# microBat.net
KiCad netlist of a schematic drawn in EAGLE
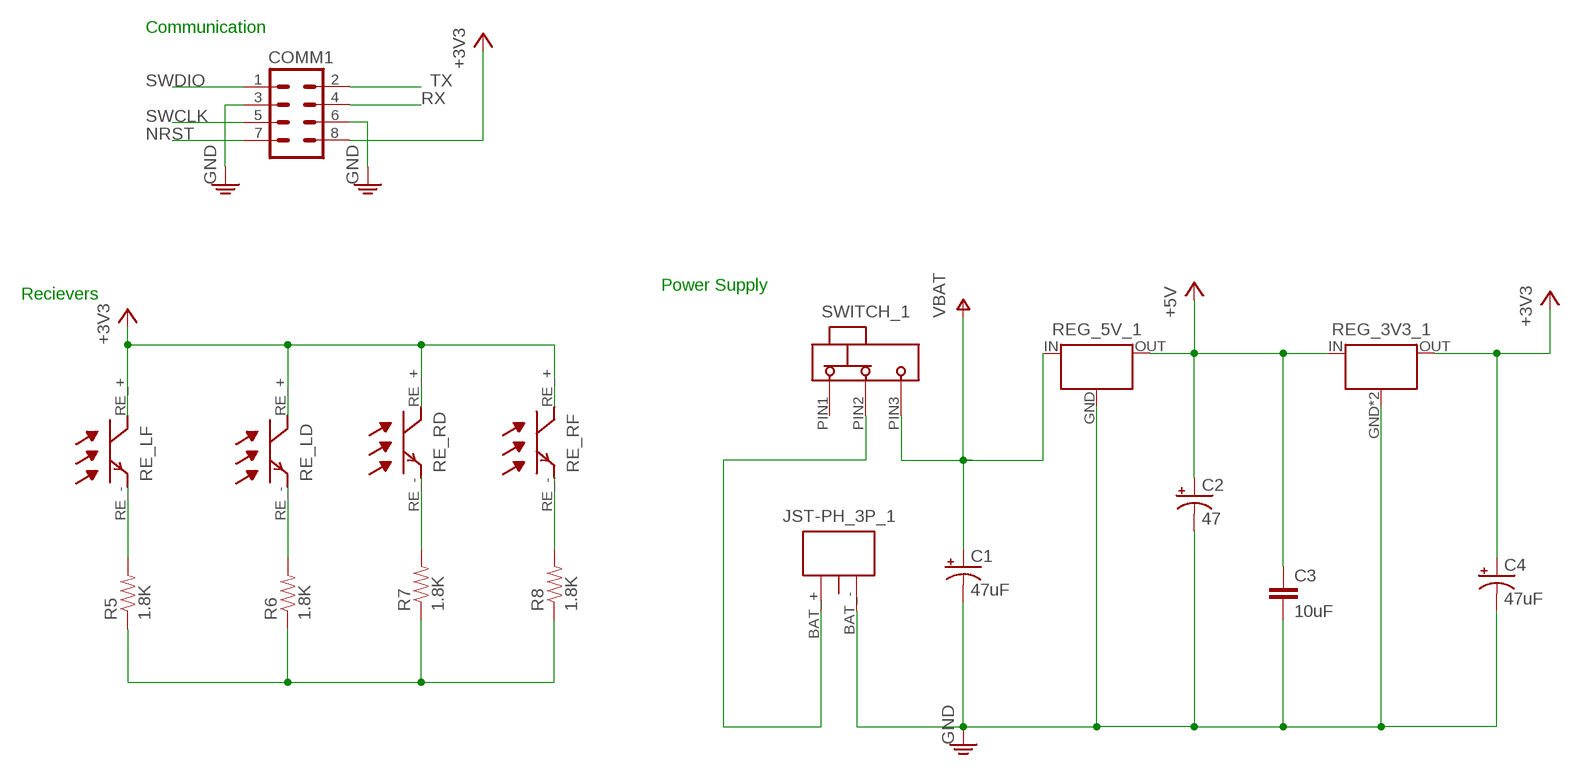
[diagram p0: schematic, sheet 1]

(export (version "E")
  (design (tool "Eeschema 10.0.6"))
  (components
    (comp (ref "C1")
      (value "47uF")
      (footprint "eagle-import:CAP_TANT_1210IN_3528MM")
      (libsource (lib "eagle-import") (part "CAP_TANT_1210IN_3528MM"))
    )
    (comp (ref "C2")
      (value "47")
      (footprint "eagle-import:CAP_TANT_1210IN_3528MM")
      (libsource (lib "eagle-import") (part "CAP_TANT_1210IN_3528MM"))
    )
    (comp (ref "C3")
      (value "10uF")
      (footprint "eagle-import:0805")
      (libsource (lib "eagle-import") (part "CAP_CERAMIC_0805IN_2012MM"))
    )
    (comp (ref "C4")
      (value "47uF")
      (footprint "eagle-import:CAP_TANT_1210IN_3528MM")
      (libsource (lib "eagle-import") (part "CAP_TANT_1210IN_3528MM"))
    )
    (comp (ref "COMM1")
      (value "M04X2")
      (footprint "eagle-import:2X4")
      (libsource (lib "eagle-import") (part "M04X2"))
    )
    (comp (ref "JST-PH_3P_1")
      (value "3PIN")
      (footprint "eagle-import:B3B-PH-K-S")
      (libsource (lib "eagle-import") (part "3PIN"))
    )
    (comp (ref "R5")
      (value "1.8K")
      (footprint "eagle-import:0805")
      (libsource (lib "eagle-import") (part "RESISTOR_0805IN_2012MM"))
    )
    (comp (ref "R6")
      (value "1.8K")
      (footprint "eagle-import:0805")
      (libsource (lib "eagle-import") (part "RESISTOR_0805IN_2012MM"))
    )
    (comp (ref "R7")
      (value "1.8K")
      (footprint "eagle-import:0805")
      (libsource (lib "eagle-import") (part "RESISTOR_0805IN_2012MM"))
    )
    (comp (ref "R8")
      (value "1.8K")
      (footprint "eagle-import:0805")
      (libsource (lib "eagle-import") (part "RESISTOR_0805IN_2012MM"))
    )
    (comp (ref "REG_3V3_1")
      (value "3V3_REG")
      (footprint "eagle-import:SOT223")
      (libsource (lib "eagle-import") (part "3V3_REG"))
    )
    (comp (ref "REG_5V_1")
      (value "REG_5V_MURATA")
      (footprint "eagle-import:5V_REG_MURATA")
      (libsource (lib "eagle-import") (part "REG_5V_MURATA"))
    )
    (comp (ref "RE_LD")
      (value "TEFT4300")
      (footprint "eagle-import:RECEIVER")
      (libsource (lib "eagle-import") (part "TEFT4300"))
    )
    (comp (ref "RE_LF")
      (value "TEFT4300")
      (footprint "eagle-import:RECEIVER")
      (libsource (lib "eagle-import") (part "TEFT4300"))
    )
    (comp (ref "RE_RD")
      (value "TEFT4300")
      (footprint "eagle-import:RECEIVER")
      (libsource (lib "eagle-import") (part "TEFT4300"))
    )
    (comp (ref "RE_RF")
      (value "TEFT4300")
      (footprint "eagle-import:RECEIVER")
      (libsource (lib "eagle-import") (part "TEFT4300"))
    )
    (comp (ref "SWITCH_1")
      (value "POLOLU_SWITCH")
      (footprint "eagle-import:POLOLU_SWITCH")
      (libsource (lib "eagle-import") (part "POLOLU_SWITCH"))
    )
  )
  (nets
    (net (code "1") (name "+3V3") (class "Default")
      (node (ref "C4") (pin "A") (pinfunction "+_A") (pintype "passive"))
      (node (ref "COMM1") (pin "8") (pinfunction "8_8") (pintype "passive"))
      (node (ref "REG_3V3_1") (pin "OUT") (pinfunction "OUT_OUT") (pintype "power_in"))
      (node (ref "RE_LD") (pin "RE_+") (pinfunction "C_RE_+") (pintype "bidirectional"))
      (node (ref "RE_LF") (pin "RE_+") (pinfunction "C_RE_+") (pintype "bidirectional"))
      (node (ref "RE_RD") (pin "RE_+") (pinfunction "C_RE_+") (pintype "bidirectional"))
      (node (ref "RE_RF") (pin "RE_+") (pinfunction "C_RE_+") (pintype "bidirectional"))
    )
    (net (code "2") (name "+5V") (class "Default")
      (node (ref "C2") (pin "A") (pinfunction "+_A") (pintype "passive"))
      (node (ref "C3") (pin "1") (pinfunction "1_1") (pintype "passive"))
      (node (ref "REG_3V3_1") (pin "IN") (pinfunction "IN_IN") (pintype "power_in"))
      (node (ref "REG_5V_1") (pin "OUT") (pinfunction "OUT_OUT") (pintype "power_in"))
    )
    (net (code "3") (name "/NRST") (class "Default")
      (node (ref "COMM1") (pin "7") (pinfunction "7_7") (pintype "passive"))
    )
    (net (code "4") (name "/RX") (class "Default")
      (node (ref "COMM1") (pin "4") (pinfunction "4_4") (pintype "passive"))
    )
    (net (code "5") (name "/SWCLK") (class "Default")
      (node (ref "COMM1") (pin "5") (pinfunction "5_5") (pintype "passive"))
    )
    (net (code "6") (name "/SWDIO") (class "Default")
      (node (ref "COMM1") (pin "1") (pinfunction "1_1") (pintype "passive"))
    )
    (net (code "7") (name "/TX") (class "Default")
      (node (ref "COMM1") (pin "2") (pinfunction "2_2") (pintype "passive"))
    )
    (net (code "8") (name "GND") (class "Default")
      (node (ref "C1") (pin "C") (pinfunction "-_C") (pintype "passive"))
      (node (ref "C2") (pin "C") (pinfunction "-_C") (pintype "passive"))
      (node (ref "C3") (pin "2") (pinfunction "2_2") (pintype "passive"))
      (node (ref "C4") (pin "C") (pinfunction "-_C") (pintype "passive"))
      (node (ref "COMM1") (pin "3") (pinfunction "3_3") (pintype "passive"))
      (node (ref "COMM1") (pin "6") (pinfunction "6_6") (pintype "passive"))
      (node (ref "JST-PH_3P_1") (pin "BAT_-") (pinfunction "BAT_-_BAT_-") (pintype "bidirectional"))
      (node (ref "REG_3V3_1") (pin "GND") (pinfunction "GND_GND") (pintype "power_in"))
      (node (ref "REG_3V3_1") (pin "GND2") (pinfunction "GND_GND2") (pintype "power_in"))
      (node (ref "REG_5V_1") (pin "GND") (pinfunction "GND_GND") (pintype "power_in"))
    )
    (net (code "9") (name "Net-(JST-PH_3P_1-PadBAT_+)") (class "Default")
      (node (ref "JST-PH_3P_1") (pin "BAT_+") (pinfunction "BAT_+_BAT_+") (pintype "bidirectional"))
      (node (ref "SWITCH_1") (pin "PIN2") (pinfunction "PIN2_PIN2") (pintype "bidirectional"))
    )
    (net (code "10") (name "Net-(R5-Pad1)") (class "Default")
      (node (ref "R5") (pin "1") (pinfunction "1_1") (pintype "passive"))
      (node (ref "R6") (pin "1") (pinfunction "1_1") (pintype "passive"))
      (node (ref "R7") (pin "1") (pinfunction "1_1") (pintype "passive"))
      (node (ref "R8") (pin "1") (pinfunction "1_1") (pintype "passive"))
    )
    (net (code "11") (name "Net-(RE_LD-E)") (class "Default")
      (node (ref "R6") (pin "2") (pinfunction "2_2") (pintype "passive"))
      (node (ref "RE_LD") (pin "RE_-") (pinfunction "E_RE_-") (pintype "bidirectional"))
    )
    (net (code "12") (name "Net-(RE_LF-E)") (class "Default")
      (node (ref "R5") (pin "2") (pinfunction "2_2") (pintype "passive"))
      (node (ref "RE_LF") (pin "RE_-") (pinfunction "E_RE_-") (pintype "bidirectional"))
    )
    (net (code "13") (name "Net-(RE_RD-E)") (class "Default")
      (node (ref "R7") (pin "2") (pinfunction "2_2") (pintype "passive"))
      (node (ref "RE_RD") (pin "RE_-") (pinfunction "E_RE_-") (pintype "bidirectional"))
    )
    (net (code "14") (name "Net-(RE_RF-E)") (class "Default")
      (node (ref "R8") (pin "2") (pinfunction "2_2") (pintype "passive"))
      (node (ref "RE_RF") (pin "RE_-") (pinfunction "E_RE_-") (pintype "bidirectional"))
    )
    (net (code "15") (name "VBAT") (class "Default")
      (node (ref "C1") (pin "A") (pinfunction "+_A") (pintype "passive"))
      (node (ref "REG_5V_1") (pin "IN") (pinfunction "IN_IN") (pintype "power_in"))
      (node (ref "SWITCH_1") (pin "PIN3") (pinfunction "PIN3_PIN3") (pintype "bidirectional"))
    )
    (net (code "16") (name "unconnected-(SWITCH_1-PadPIN1)") (class "Default")
      (node (ref "SWITCH_1") (pin "PIN1") (pinfunction "PIN1_PIN1") (pintype "bidirectional"))
    )
  )
)
